# config-bank1.net
KiCad netlist of a schematic drawn in Altium Designer
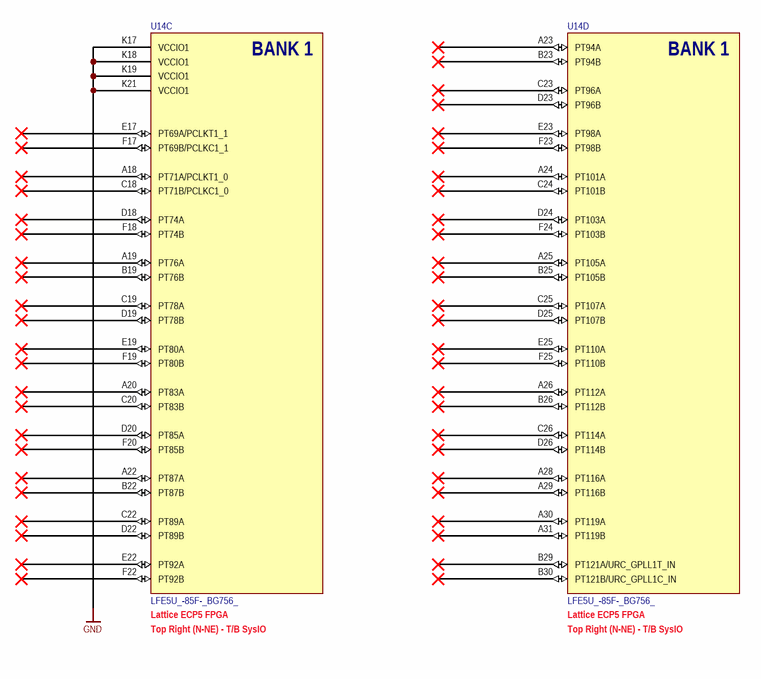
[diagram p0: config-bank1.SchDoc]

(export (version "E")
  (design (tool "Eeschema 10.0.6"))
  (components
    (comp (ref "U14")
      (value "LFE5U_-85F-_BG756_")
      (footprint "lattice:caBGA756")
      (description "ECP5 FPGA, 85k LUT, 756-caBGA")
      (fields (field (name "MANUFACTURER") "Lattice Semiconductor"))
      (libsource (lib "lattice") (part "LFE5U_-85F-_BG756_"))
    )
  )
  (nets
    (net (code "1") (name "GND") (class "Default")
      (node (ref "U14") (pin "K17") (pinfunction "VCCIO1_K17") (pintype "power_in"))
      (node (ref "U14") (pin "K18") (pinfunction "VCCIO1_K18") (pintype "power_in"))
      (node (ref "U14") (pin "K19") (pinfunction "VCCIO1_K19") (pintype "power_in"))
      (node (ref "U14") (pin "K21") (pinfunction "VCCIO1_K21") (pintype "power_in"))
    )
    (net (code "2") (name "unconnected-(U14C-PT69A{slash}PCLKT1_1-PadE17)") (class "Default")
      (node (ref "U14") (pin "E17") (pinfunction "PT69A/PCLKT1_1_E17") (pintype "bidirectional+no_connect"))
    )
    (net (code "3") (name "unconnected-(U14C-PT69B{slash}PCLKC1_1-PadF17)") (class "Default")
      (node (ref "U14") (pin "F17") (pinfunction "PT69B/PCLKC1_1_F17") (pintype "bidirectional+no_connect"))
    )
    (net (code "4") (name "unconnected-(U14C-PT71A{slash}PCLKT1_0-PadA18)") (class "Default")
      (node (ref "U14") (pin "A18") (pinfunction "PT71A/PCLKT1_0_A18") (pintype "bidirectional+no_connect"))
    )
    (net (code "5") (name "unconnected-(U14C-PT71B{slash}PCLKC1_0-PadC18)") (class "Default")
      (node (ref "U14") (pin "C18") (pinfunction "PT71B/PCLKC1_0_C18") (pintype "bidirectional+no_connect"))
    )
    (net (code "6") (name "unconnected-(U14C-PT74A-PadD18)") (class "Default")
      (node (ref "U14") (pin "D18") (pinfunction "PT74A_D18") (pintype "bidirectional+no_connect"))
    )
    (net (code "7") (name "unconnected-(U14C-PT74B-PadF18)") (class "Default")
      (node (ref "U14") (pin "F18") (pinfunction "PT74B_F18") (pintype "bidirectional+no_connect"))
    )
    (net (code "8") (name "unconnected-(U14C-PT76A-PadA19)") (class "Default")
      (node (ref "U14") (pin "A19") (pinfunction "PT76A_A19") (pintype "bidirectional+no_connect"))
    )
    (net (code "9") (name "unconnected-(U14C-PT76B-PadB19)") (class "Default")
      (node (ref "U14") (pin "B19") (pinfunction "PT76B_B19") (pintype "bidirectional+no_connect"))
    )
    (net (code "10") (name "unconnected-(U14C-PT78A-PadC19)") (class "Default")
      (node (ref "U14") (pin "C19") (pinfunction "PT78A_C19") (pintype "bidirectional+no_connect"))
    )
    (net (code "11") (name "unconnected-(U14C-PT78B-PadD19)") (class "Default")
      (node (ref "U14") (pin "D19") (pinfunction "PT78B_D19") (pintype "bidirectional+no_connect"))
    )
    (net (code "12") (name "unconnected-(U14C-PT80A-PadE19)") (class "Default")
      (node (ref "U14") (pin "E19") (pinfunction "PT80A_E19") (pintype "bidirectional+no_connect"))
    )
    (net (code "13") (name "unconnected-(U14C-PT80B-PadF19)") (class "Default")
      (node (ref "U14") (pin "F19") (pinfunction "PT80B_F19") (pintype "bidirectional+no_connect"))
    )
    (net (code "14") (name "unconnected-(U14C-PT83A-PadA20)") (class "Default")
      (node (ref "U14") (pin "A20") (pinfunction "PT83A_A20") (pintype "bidirectional+no_connect"))
    )
    (net (code "15") (name "unconnected-(U14C-PT83B-PadC20)") (class "Default")
      (node (ref "U14") (pin "C20") (pinfunction "PT83B_C20") (pintype "bidirectional+no_connect"))
    )
    (net (code "16") (name "unconnected-(U14C-PT85A-PadD20)") (class "Default")
      (node (ref "U14") (pin "D20") (pinfunction "PT85A_D20") (pintype "bidirectional+no_connect"))
    )
    (net (code "17") (name "unconnected-(U14C-PT85B-PadF20)") (class "Default")
      (node (ref "U14") (pin "F20") (pinfunction "PT85B_F20") (pintype "bidirectional+no_connect"))
    )
    (net (code "18") (name "unconnected-(U14C-PT87A-PadA22)") (class "Default")
      (node (ref "U14") (pin "A22") (pinfunction "PT87A_A22") (pintype "bidirectional+no_connect"))
    )
    (net (code "19") (name "unconnected-(U14C-PT87B-PadB22)") (class "Default")
      (node (ref "U14") (pin "B22") (pinfunction "PT87B_B22") (pintype "bidirectional+no_connect"))
    )
    (net (code "20") (name "unconnected-(U14C-PT89A-PadC22)") (class "Default")
      (node (ref "U14") (pin "C22") (pinfunction "PT89A_C22") (pintype "bidirectional+no_connect"))
    )
    (net (code "21") (name "unconnected-(U14C-PT89B-PadD22)") (class "Default")
      (node (ref "U14") (pin "D22") (pinfunction "PT89B_D22") (pintype "bidirectional+no_connect"))
    )
    (net (code "22") (name "unconnected-(U14C-PT92A-PadE22)") (class "Default")
      (node (ref "U14") (pin "E22") (pinfunction "PT92A_E22") (pintype "bidirectional+no_connect"))
    )
    (net (code "23") (name "unconnected-(U14C-PT92B-PadF22)") (class "Default")
      (node (ref "U14") (pin "F22") (pinfunction "PT92B_F22") (pintype "bidirectional+no_connect"))
    )
    (net (code "24") (name "unconnected-(U14D-PT94A-PadA23)") (class "Default")
      (node (ref "U14") (pin "A23") (pinfunction "PT94A_A23") (pintype "bidirectional+no_connect"))
    )
    (net (code "25") (name "unconnected-(U14D-PT94B-PadB23)") (class "Default")
      (node (ref "U14") (pin "B23") (pinfunction "PT94B_B23") (pintype "bidirectional+no_connect"))
    )
    (net (code "26") (name "unconnected-(U14D-PT96A-PadC23)") (class "Default")
      (node (ref "U14") (pin "C23") (pinfunction "PT96A_C23") (pintype "bidirectional+no_connect"))
    )
    (net (code "27") (name "unconnected-(U14D-PT96B-PadD23)") (class "Default")
      (node (ref "U14") (pin "D23") (pinfunction "PT96B_D23") (pintype "bidirectional+no_connect"))
    )
    (net (code "28") (name "unconnected-(U14D-PT98A-PadE23)") (class "Default")
      (node (ref "U14") (pin "E23") (pinfunction "PT98A_E23") (pintype "bidirectional+no_connect"))
    )
    (net (code "29") (name "unconnected-(U14D-PT98B-PadF23)") (class "Default")
      (node (ref "U14") (pin "F23") (pinfunction "PT98B_F23") (pintype "bidirectional+no_connect"))
    )
    (net (code "30") (name "unconnected-(U14D-PT101A-PadA24)") (class "Default")
      (node (ref "U14") (pin "A24") (pinfunction "PT101A_A24") (pintype "bidirectional+no_connect"))
    )
    (net (code "31") (name "unconnected-(U14D-PT101B-PadC24)") (class "Default")
      (node (ref "U14") (pin "C24") (pinfunction "PT101B_C24") (pintype "bidirectional+no_connect"))
    )
    (net (code "32") (name "unconnected-(U14D-PT103A-PadD24)") (class "Default")
      (node (ref "U14") (pin "D24") (pinfunction "PT103A_D24") (pintype "bidirectional+no_connect"))
    )
    (net (code "33") (name "unconnected-(U14D-PT103B-PadF24)") (class "Default")
      (node (ref "U14") (pin "F24") (pinfunction "PT103B_F24") (pintype "bidirectional+no_connect"))
    )
    (net (code "34") (name "unconnected-(U14D-PT105A-PadA25)") (class "Default")
      (node (ref "U14") (pin "A25") (pinfunction "PT105A_A25") (pintype "bidirectional+no_connect"))
    )
    (net (code "35") (name "unconnected-(U14D-PT105B-PadB25)") (class "Default")
      (node (ref "U14") (pin "B25") (pinfunction "PT105B_B25") (pintype "bidirectional+no_connect"))
    )
    (net (code "36") (name "unconnected-(U14D-PT107A-PadC25)") (class "Default")
      (node (ref "U14") (pin "C25") (pinfunction "PT107A_C25") (pintype "bidirectional+no_connect"))
    )
    (net (code "37") (name "unconnected-(U14D-PT107B-PadD25)") (class "Default")
      (node (ref "U14") (pin "D25") (pinfunction "PT107B_D25") (pintype "bidirectional+no_connect"))
    )
    (net (code "38") (name "unconnected-(U14D-PT110A-PadE25)") (class "Default")
      (node (ref "U14") (pin "E25") (pinfunction "PT110A_E25") (pintype "bidirectional+no_connect"))
    )
    (net (code "39") (name "unconnected-(U14D-PT110B-PadF25)") (class "Default")
      (node (ref "U14") (pin "F25") (pinfunction "PT110B_F25") (pintype "bidirectional+no_connect"))
    )
    (net (code "40") (name "unconnected-(U14D-PT112A-PadA26)") (class "Default")
      (node (ref "U14") (pin "A26") (pinfunction "PT112A_A26") (pintype "bidirectional+no_connect"))
    )
    (net (code "41") (name "unconnected-(U14D-PT112B-PadB26)") (class "Default")
      (node (ref "U14") (pin "B26") (pinfunction "PT112B_B26") (pintype "bidirectional+no_connect"))
    )
    (net (code "42") (name "unconnected-(U14D-PT114A-PadC26)") (class "Default")
      (node (ref "U14") (pin "C26") (pinfunction "PT114A_C26") (pintype "bidirectional+no_connect"))
    )
    (net (code "43") (name "unconnected-(U14D-PT114B-PadD26)") (class "Default")
      (node (ref "U14") (pin "D26") (pinfunction "PT114B_D26") (pintype "bidirectional+no_connect"))
    )
    (net (code "44") (name "unconnected-(U14D-PT116A-PadA28)") (class "Default")
      (node (ref "U14") (pin "A28") (pinfunction "PT116A_A28") (pintype "bidirectional+no_connect"))
    )
    (net (code "45") (name "unconnected-(U14D-PT116B-PadA29)") (class "Default")
      (node (ref "U14") (pin "A29") (pinfunction "PT116B_A29") (pintype "bidirectional+no_connect"))
    )
    (net (code "46") (name "unconnected-(U14D-PT119A-PadA30)") (class "Default")
      (node (ref "U14") (pin "A30") (pinfunction "PT119A_A30") (pintype "bidirectional+no_connect"))
    )
    (net (code "47") (name "unconnected-(U14D-PT119B-PadA31)") (class "Default")
      (node (ref "U14") (pin "A31") (pinfunction "PT119B_A31") (pintype "bidirectional+no_connect"))
    )
    (net (code "48") (name "unconnected-(U14D-PT121A{slash}URC_GPLL1T_IN-PadB29)") (class "Default")
      (node (ref "U14") (pin "B29") (pinfunction "PT121A/URC_GPLL1T_IN_B29") (pintype "bidirectional+no_connect"))
    )
    (net (code "49") (name "unconnected-(U14D-PT121B{slash}URC_GPLL1C_IN-PadB30)") (class "Default")
      (node (ref "U14") (pin "B30") (pinfunction "PT121B/URC_GPLL1C_IN_B30") (pintype "bidirectional+no_connect"))
    )
  )
)
